# ESP8266-01_Solid_State_Relay_2016-01-18.net
KiCad netlist of a schematic drawn in EAGLE
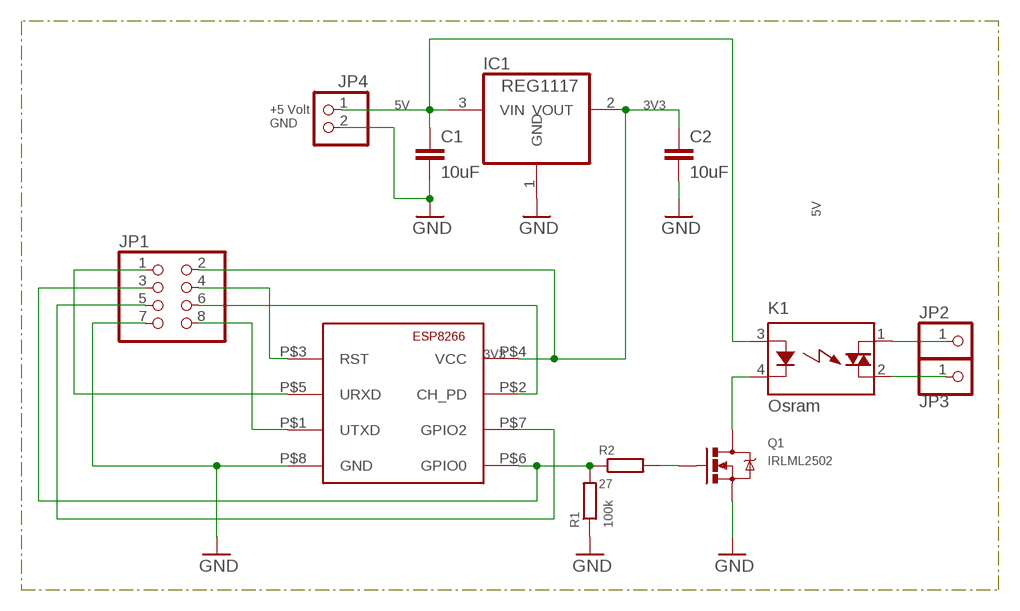
[diagram p0: schematic, sheet 1]

(export (version "E")
  (design (tool "Eeschema 10.0.6"))
  (components
    (comp (ref "C1")
      (value "10uF")
      (footprint "eagle-import:C1206")
      (libsource (lib "eagle-import") (part "C-EUC1206"))
    )
    (comp (ref "C2")
      (value "10uF")
      (footprint "eagle-import:C1206")
      (libsource (lib "eagle-import") (part "C-EUC1206"))
    )
    (comp (ref "IC1")
      (value "REG1117")
      (footprint "eagle-import:SOT223")
      (libsource (lib "eagle-import") (part "REG1117"))
    )
    (comp (ref "JP1")
      (value "PINHD-2X4")
      (footprint "eagle-import:2X04")
      (libsource (lib "eagle-import") (part "PINHD-2X4"))
    )
    (comp (ref "JP2")
      (value "PINHD-1X1")
      (footprint "eagle-import:1X01")
      (libsource (lib "eagle-import") (part "PINHD-1X1"))
    )
    (comp (ref "JP3")
      (value "PINHD-1X1")
      (footprint "eagle-import:1X01")
      (libsource (lib "eagle-import") (part "PINHD-1X1"))
    )
    (comp (ref "JP4")
      (value "PINHD-1X2")
      (footprint "eagle-import:1X02")
      (libsource (lib "eagle-import") (part "PINHD-1X2"))
    )
    (comp (ref "K1")
      (value "Osram")
      (footprint "eagle-import:S2XXEX")
      (libsource (lib "eagle-import") (part "S202SE1"))
    )
    (comp (ref "Q1")
      (value "IRLML2502")
      (footprint "eagle-import:SOT23-3")
      (libsource (lib "eagle-import") (part "MOSFET-NCHANNELAO3404A"))
    )
    (comp (ref "R1")
      (value "100k")
      (footprint "eagle-import:R0805")
      (libsource (lib "eagle-import") (part "R-EU_R0805"))
    )
    (comp (ref "R2")
      (value "27")
      (footprint "eagle-import:R0805")
      (libsource (lib "eagle-import") (part "R-EU_R0805"))
    )
    (comp (ref "U$1")
      (value "ESP8266-01")
      (footprint "eagle-import:ESP-01")
      (libsource (lib "eagle-import") (part "ESP8266-01"))
    )
  )
  (nets
    (net (code "1") (name "/3V3") (class "Default")
      (node (ref "C2") (pin "1") (pinfunction "1_1") (pintype "passive"))
      (node (ref "IC1") (pin "2") (pinfunction "VOUT_2") (pintype "output"))
      (node (ref "JP1") (pin "2") (pinfunction "2_2") (pintype "passive"))
      (node (ref "U$1") (pin "P$4") (pinfunction "VCC_P$4") (pintype "bidirectional"))
    )
    (net (code "2") (name "/5V") (class "Default")
      (node (ref "C1") (pin "1") (pinfunction "1_1") (pintype "passive"))
      (node (ref "IC1") (pin "3") (pinfunction "VIN_3") (pintype "input"))
      (node (ref "JP4") (pin "1") (pinfunction "1_1") (pintype "passive"))
      (node (ref "K1") (pin "3") (pinfunction "A_3") (pintype "passive"))
    )
    (net (code "3") (name "GND") (class "Default")
      (node (ref "C1") (pin "2") (pinfunction "2_2") (pintype "passive"))
      (node (ref "C2") (pin "2") (pinfunction "2_2") (pintype "passive"))
      (node (ref "IC1") (pin "1") (pinfunction "GND_1") (pintype "power_in"))
      (node (ref "JP1") (pin "7") (pinfunction "7_7") (pintype "passive"))
      (node (ref "JP4") (pin "2") (pinfunction "2_2") (pintype "passive"))
      (node (ref "Q1") (pin "2") (pinfunction "S_2") (pintype "passive"))
      (node (ref "R1") (pin "1") (pinfunction "1_1") (pintype "passive"))
      (node (ref "U$1") (pin "P$8") (pinfunction "GND_P$8") (pintype "bidirectional"))
    )
    (net (code "4") (name "Net-(K1-DS1)") (class "Default")
      (node (ref "JP2") (pin "1") (pinfunction "1_1") (pintype "passive"))
      (node (ref "K1") (pin "1") (pinfunction "DS1_1") (pintype "passive"))
    )
    (net (code "5") (name "Net-(K1-DS2)") (class "Default")
      (node (ref "JP3") (pin "1") (pinfunction "1_1") (pintype "passive"))
      (node (ref "K1") (pin "2") (pinfunction "DS2_2") (pintype "passive"))
    )
    (net (code "6") (name "Net-(K1-K)") (class "Default")
      (node (ref "K1") (pin "4") (pinfunction "K_4") (pintype "passive"))
      (node (ref "Q1") (pin "3") (pinfunction "D_3") (pintype "passive"))
    )
    (net (code "7") (name "Net-(Q1-G)") (class "Default")
      (node (ref "Q1") (pin "1") (pinfunction "G_1") (pintype "passive"))
      (node (ref "R2") (pin "2") (pinfunction "2_2") (pintype "passive"))
    )
    (net (code "8") (name "Net-(U$1-CH_PD)") (class "Default")
      (node (ref "JP1") (pin "6") (pinfunction "6_6") (pintype "passive"))
      (node (ref "U$1") (pin "P$2") (pinfunction "CH_PD_P$2") (pintype "bidirectional"))
    )
    (net (code "9") (name "Net-(U$1-GPIO0)") (class "Default")
      (node (ref "JP1") (pin "3") (pinfunction "3_3") (pintype "passive"))
      (node (ref "R1") (pin "2") (pinfunction "2_2") (pintype "passive"))
      (node (ref "R2") (pin "1") (pinfunction "1_1") (pintype "passive"))
      (node (ref "U$1") (pin "P$6") (pinfunction "GPIO0_P$6") (pintype "bidirectional"))
    )
    (net (code "10") (name "Net-(U$1-GPIO2)") (class "Default")
      (node (ref "JP1") (pin "5") (pinfunction "5_5") (pintype "passive"))
      (node (ref "U$1") (pin "P$7") (pinfunction "GPIO2_P$7") (pintype "bidirectional"))
    )
    (net (code "11") (name "Net-(U$1-RST)") (class "Default")
      (node (ref "JP1") (pin "4") (pinfunction "4_4") (pintype "passive"))
      (node (ref "U$1") (pin "P$3") (pinfunction "RST_P$3") (pintype "bidirectional"))
    )
    (net (code "12") (name "Net-(U$1-URXD)") (class "Default")
      (node (ref "JP1") (pin "1") (pinfunction "1_1") (pintype "passive"))
      (node (ref "U$1") (pin "P$5") (pinfunction "URXD_P$5") (pintype "bidirectional"))
    )
    (net (code "13") (name "Net-(U$1-UTXD)") (class "Default")
      (node (ref "JP1") (pin "8") (pinfunction "8_8") (pintype "passive"))
      (node (ref "U$1") (pin "P$1") (pinfunction "UTXD_P$1") (pintype "bidirectional"))
    )
  )
)
